# Nodo_univ.net
KiCad netlist of a schematic drawn in EAGLE
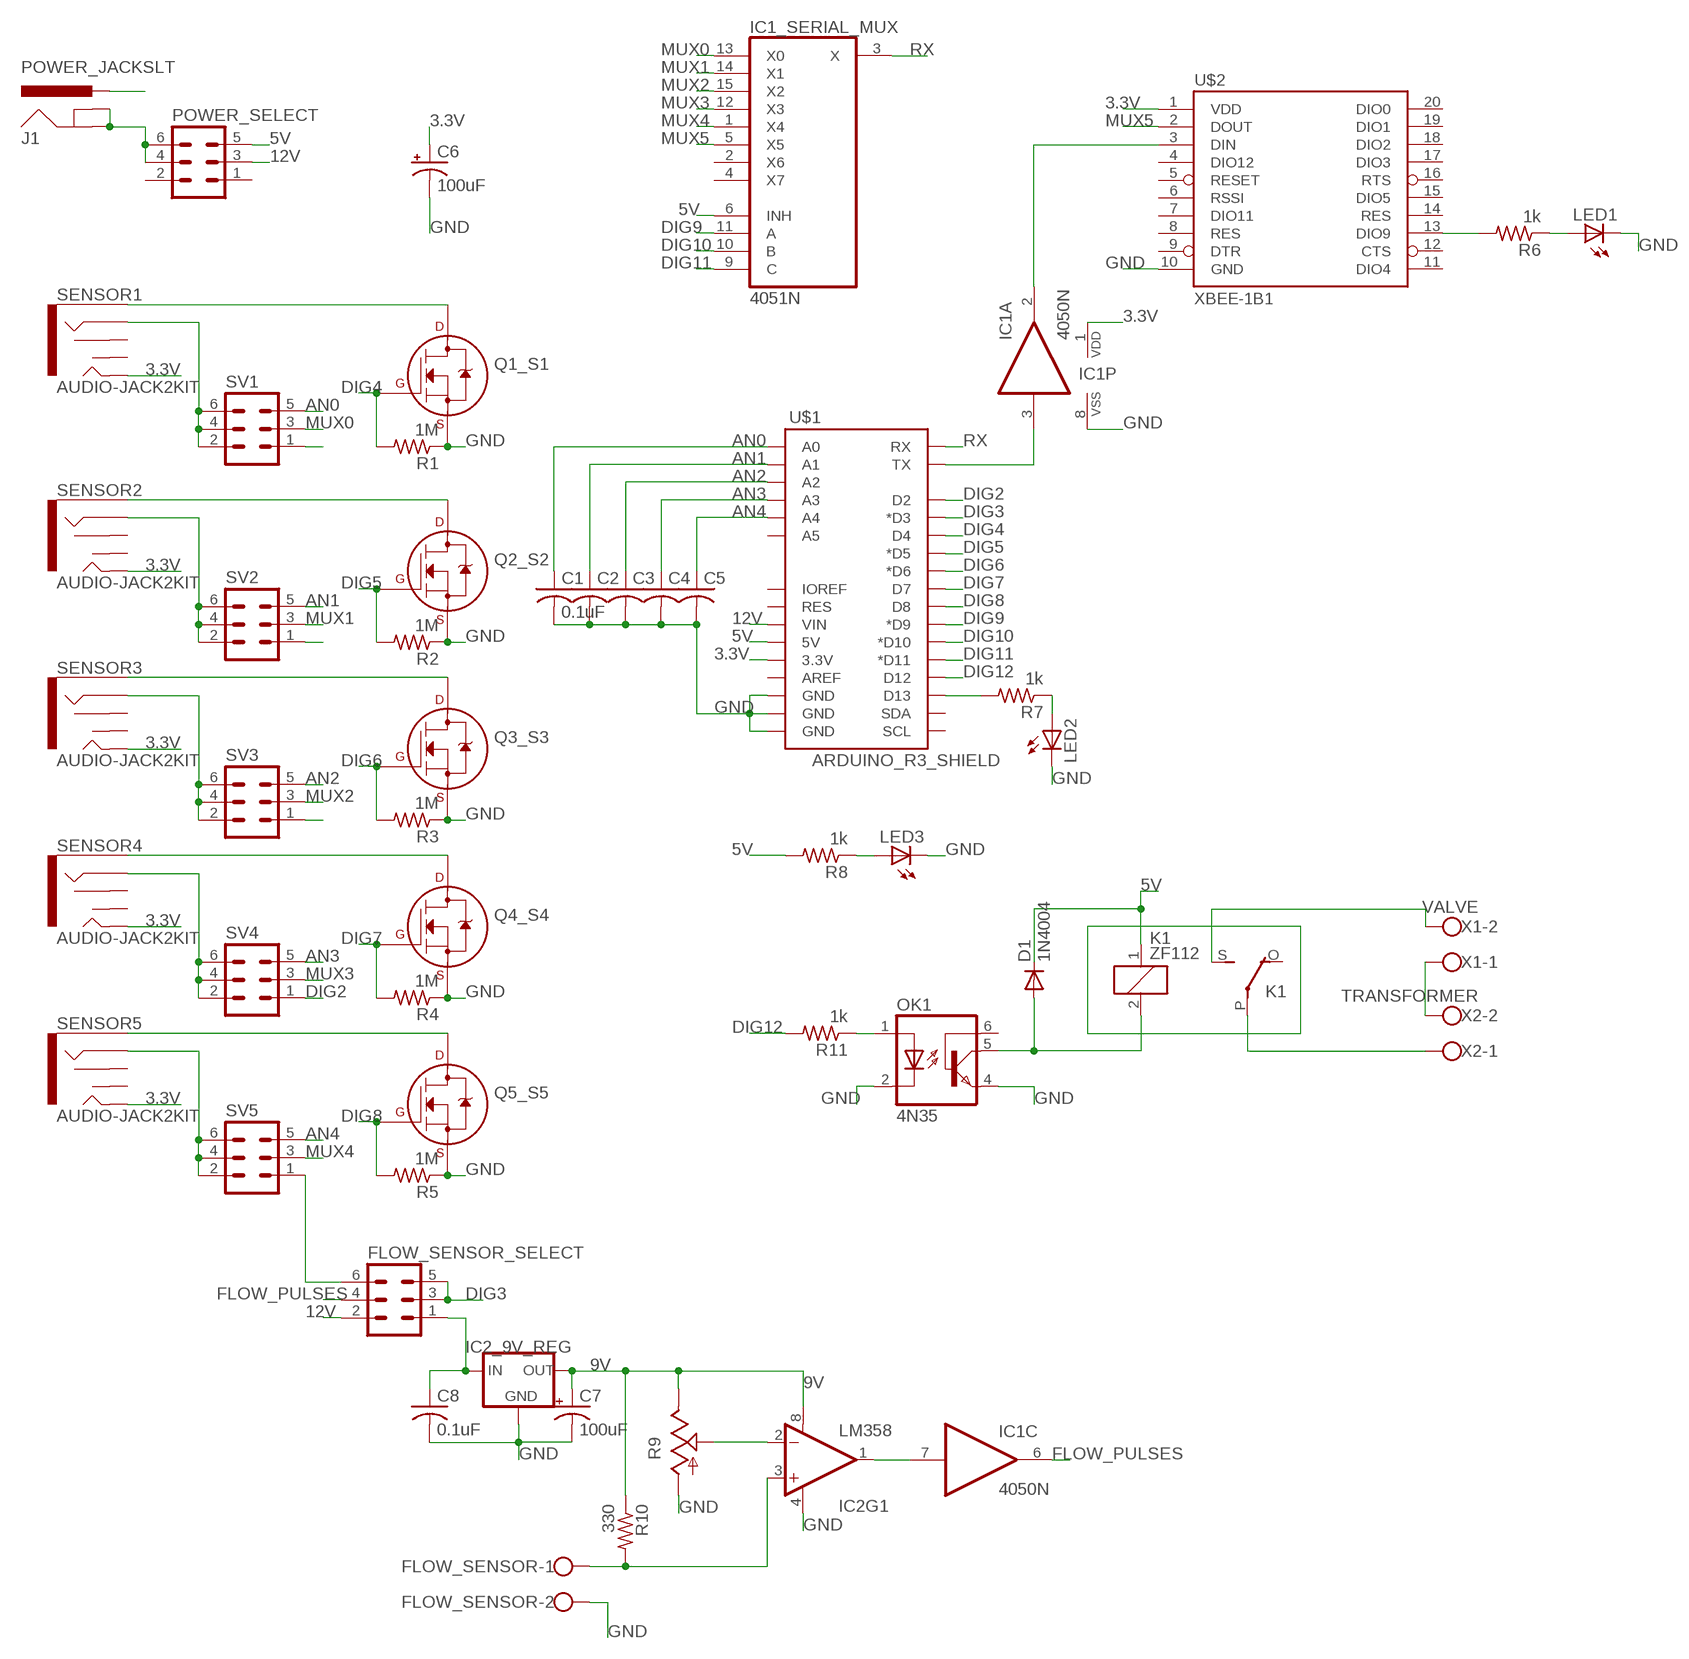
[diagram p0: schematic, sheet 1]

(export (version "E")
  (design (tool "Eeschema 10.0.6"))
  (components
    (comp (ref "C1")
      (value "0.1uF")
      (footprint "eagle-import:C025-025X050")
      (libsource (lib "eagle-import") (part "C-US025-025X050"))
    )
    (comp (ref "C2")
      (value "C-US025-025X050")
      (footprint "eagle-import:C025-025X050")
      (libsource (lib "eagle-import") (part "C-US025-025X050"))
    )
    (comp (ref "C3")
      (value "C-US025-025X050")
      (footprint "eagle-import:C025-025X050")
      (libsource (lib "eagle-import") (part "C-US025-025X050"))
    )
    (comp (ref "C4")
      (value "C-US025-025X050")
      (footprint "eagle-import:C025-025X050")
      (libsource (lib "eagle-import") (part "C-US025-025X050"))
    )
    (comp (ref "C5")
      (value "C-US025-025X050")
      (footprint "eagle-import:C025-025X050")
      (libsource (lib "eagle-import") (part "C-US025-025X050"))
    )
    (comp (ref "C6")
      (value "100uF")
      (footprint "eagle-import:CPOL-RADIAL-100UF-25V")
      (libsource (lib "eagle-import") (part "CAP_POLPTH1"))
    )
    (comp (ref "C7")
      (value "100uF")
      (footprint "eagle-import:CPOL-RADIAL-100UF-25V")
      (libsource (lib "eagle-import") (part "CAP_POLPTH1"))
    )
    (comp (ref "C8")
      (value "0.1uF")
      (footprint "eagle-import:C025-025X050")
      (libsource (lib "eagle-import") (part "C-US025-025X050"))
    )
    (comp (ref "D1")
      (value "1N4004")
      (footprint "eagle-import:DO41-10")
      (libsource (lib "eagle-import") (part "1N4004"))
    )
    (comp (ref "FLOW_SENSOR")
      (value "W237-102")
      (footprint "eagle-import:W237-102")
      (fields (field (name "MPN") "237-102"))
      (libsource (lib "eagle-import") (part "W237-102"))
    )
    (comp (ref "FLOW_SENSOR_SELECT")
      (value "MA03-2")
      (footprint "eagle-import:MA03-2")
      (libsource (lib "eagle-import") (part "MA03-2"))
    )
    (comp (ref "IC1")
      (value "4050N")
      (footprint "eagle-import:DIL16")
      (libsource (lib "eagle-import") (part "4050N"))
    )
    (comp (ref "IC1_SERIAL_MUX")
      (value "4051N")
      (footprint "eagle-import:DIL16")
      (libsource (lib "eagle-import") (part "4051N"))
    )
    (comp (ref "IC2")
      (value "LM358")
      (footprint "eagle-import:DIP08")
      (libsource (lib "eagle-import") (part "LM358"))
    )
    (comp (ref "IC2_9V_REG")
      (value "78XXL")
      (footprint "eagle-import:78XXL")
      (libsource (lib "eagle-import") (part "78XXL"))
    )
    (comp (ref "J1")
      (value "POWER_JACKSLT")
      (footprint "eagle-import:POWER_JACK_SLOT")
      (libsource (lib "eagle-import") (part "POWER_JACKSLT"))
    )
    (comp (ref "K1")
      (value "ZF112")
      (footprint "eagle-import:ZF112")
      (libsource (lib "eagle-import") (part "ZF112"))
    )
    (comp (ref "LED1")
      (value "LED3MM")
      (footprint "eagle-import:LED3MM")
      (libsource (lib "eagle-import") (part "LED3MM"))
    )
    (comp (ref "LED2")
      (value "LED3MM")
      (footprint "eagle-import:LED3MM")
      (libsource (lib "eagle-import") (part "LED3MM"))
    )
    (comp (ref "LED3")
      (value "LED3MM")
      (footprint "eagle-import:LED3MM")
      (libsource (lib "eagle-import") (part "LED3MM"))
    )
    (comp (ref "OK1")
      (value "4N35")
      (footprint "eagle-import:DIL06")
      (fields (field (name "MF") "FAIRCHILD SEMICONDUCTOR"))
      (libsource (lib "eagle-import") (part "4N35"))
    )
    (comp (ref "POWER_SELECT")
      (value "MA03-2")
      (footprint "eagle-import:MA03-2")
      (libsource (lib "eagle-import") (part "MA03-2"))
    )
    (comp (ref "Q1_S1")
      (value "2N7000_TO92")
      (footprint "eagle-import:TO-92")
      (libsource (lib "eagle-import") (part "2N700_TO920"))
    )
    (comp (ref "Q2_S2")
      (value "2N7000_TO92")
      (footprint "eagle-import:TO-92")
      (libsource (lib "eagle-import") (part "2N700_TO920"))
    )
    (comp (ref "Q3_S3")
      (value "2N7000_TO92")
      (footprint "eagle-import:TO-92")
      (libsource (lib "eagle-import") (part "2N700_TO920"))
    )
    (comp (ref "Q4_S4")
      (value "2N7000_TO92")
      (footprint "eagle-import:TO-92")
      (libsource (lib "eagle-import") (part "2N700_TO920"))
    )
    (comp (ref "Q5_S5")
      (value "2N7000_TO92")
      (footprint "eagle-import:TO-92")
      (libsource (lib "eagle-import") (part "2N700_TO920"))
    )
    (comp (ref "R1")
      (value "1M")
      (footprint "eagle-import:0207_10")
      (libsource (lib "eagle-import") (part "R-US_0207/10"))
    )
    (comp (ref "R2")
      (value "1M")
      (footprint "eagle-import:0207_10")
      (libsource (lib "eagle-import") (part "R-US_0207/10"))
    )
    (comp (ref "R3")
      (value "1M")
      (footprint "eagle-import:0207_10")
      (libsource (lib "eagle-import") (part "R-US_0207/10"))
    )
    (comp (ref "R4")
      (value "1M")
      (footprint "eagle-import:0207_10")
      (libsource (lib "eagle-import") (part "R-US_0207/10"))
    )
    (comp (ref "R5")
      (value "1M")
      (footprint "eagle-import:0207_10")
      (libsource (lib "eagle-import") (part "R-US_0207/10"))
    )
    (comp (ref "R6")
      (value "1k")
      (footprint "eagle-import:0207_10")
      (libsource (lib "eagle-import") (part "R-US_0207/10"))
    )
    (comp (ref "R7")
      (value "1k")
      (footprint "eagle-import:0207_10")
      (libsource (lib "eagle-import") (part "R-US_0207/10"))
    )
    (comp (ref "R8")
      (value "1k")
      (footprint "eagle-import:0207_10")
      (libsource (lib "eagle-import") (part "R-US_0207/10"))
    )
    (comp (ref "R9")
      (value "TRIM_US-B64Y")
      (footprint "eagle-import:B64Y")
      (libsource (lib "eagle-import") (part "TRIM_US-B64Y"))
    )
    (comp (ref "R10")
      (value "330")
      (footprint "eagle-import:0207_10")
      (libsource (lib "eagle-import") (part "R-US_0207/10"))
    )
    (comp (ref "R11")
      (value "1k")
      (footprint "eagle-import:0207_10")
      (libsource (lib "eagle-import") (part "R-US_0207/10"))
    )
    (comp (ref "SENSOR1")
      (value "AUDIO-JACK2KIT")
      (footprint "eagle-import:AUDIO-JACK-KIT")
      (libsource (lib "eagle-import") (part "AUDIO-JACK2KIT"))
    )
    (comp (ref "SENSOR2")
      (value "AUDIO-JACK2KIT")
      (footprint "eagle-import:AUDIO-JACK-KIT")
      (libsource (lib "eagle-import") (part "AUDIO-JACK2KIT"))
    )
    (comp (ref "SENSOR3")
      (value "AUDIO-JACK2KIT")
      (footprint "eagle-import:AUDIO-JACK-KIT")
      (libsource (lib "eagle-import") (part "AUDIO-JACK2KIT"))
    )
    (comp (ref "SENSOR4")
      (value "AUDIO-JACK2KIT")
      (footprint "eagle-import:AUDIO-JACK-KIT")
      (libsource (lib "eagle-import") (part "AUDIO-JACK2KIT"))
    )
    (comp (ref "SENSOR5")
      (value "AUDIO-JACK2KIT")
      (footprint "eagle-import:AUDIO-JACK-KIT")
      (libsource (lib "eagle-import") (part "AUDIO-JACK2KIT"))
    )
    (comp (ref "SV1")
      (value "MA03-2")
      (footprint "eagle-import:MA03-2")
      (libsource (lib "eagle-import") (part "MA03-2"))
    )
    (comp (ref "SV2")
      (value "MA03-2")
      (footprint "eagle-import:MA03-2")
      (libsource (lib "eagle-import") (part "MA03-2"))
    )
    (comp (ref "SV3")
      (value "MA03-2")
      (footprint "eagle-import:MA03-2")
      (libsource (lib "eagle-import") (part "MA03-2"))
    )
    (comp (ref "SV4")
      (value "MA03-2")
      (footprint "eagle-import:MA03-2")
      (libsource (lib "eagle-import") (part "MA03-2"))
    )
    (comp (ref "SV5")
      (value "MA03-2")
      (footprint "eagle-import:MA03-2")
      (libsource (lib "eagle-import") (part "MA03-2"))
    )
    (comp (ref "U$1")
      (value "ARDUINO_R3_SHIELD")
      (footprint "eagle-import:UNO_R3_SHIELD")
      (libsource (lib "eagle-import") (part "ARDUINO_R3_SHIELD"))
    )
    (comp (ref "U$2")
      (value "XBEE-1B1")
      (footprint "eagle-import:XBEE-1")
      (libsource (lib "eagle-import") (part "XBEE-1B1"))
    )
    (comp (ref "X1")
      (value "VALVE")
      (footprint "eagle-import:W237-102")
      (fields (field (name "MPN") "237-102"))
      (libsource (lib "eagle-import") (part "W237-102"))
    )
    (comp (ref "X2")
      (value "TRANSFORMER")
      (footprint "eagle-import:W237-102")
      (fields (field (name "MPN") "237-102"))
      (libsource (lib "eagle-import") (part "W237-102"))
    )
  )
  (nets
    (net (code "1") (name "/3.3V") (class "Default")
      (node (ref "C6") (pin "1") (pinfunction "+_1") (pintype "passive"))
      (node (ref "IC1") (pin "1") (pinfunction "VDD_1") (pintype "power_in"))
      (node (ref "SENSOR1") (pin "TIP") (pinfunction "TIP_TIP") (pintype "bidirectional"))
      (node (ref "SENSOR2") (pin "TIP") (pinfunction "TIP_TIP") (pintype "bidirectional"))
      (node (ref "SENSOR3") (pin "TIP") (pinfunction "TIP_TIP") (pintype "bidirectional"))
      (node (ref "SENSOR4") (pin "TIP") (pinfunction "TIP_TIP") (pintype "bidirectional"))
      (node (ref "SENSOR5") (pin "TIP") (pinfunction "TIP_TIP") (pintype "bidirectional"))
      (node (ref "U$1") (pin "3.3V") (pinfunction "3.3V_3.3V") (pintype "bidirectional"))
      (node (ref "U$2") (pin "1") (pinfunction "VDD_1") (pintype "power_in"))
    )
    (net (code "2") (name "/5V") (class "Default")
      (node (ref "D1") (pin "C") (pinfunction "C_C") (pintype "passive"))
      (node (ref "IC1_SERIAL_MUX") (pin "6") (pinfunction "INH_6") (pintype "input"))
      (node (ref "K1") (pin "1") (pinfunction "1_1") (pintype "passive"))
      (node (ref "POWER_SELECT") (pin "5") (pinfunction "5_5") (pintype "passive"))
      (node (ref "R8") (pin "2") (pinfunction "2_2") (pintype "passive"))
      (node (ref "U$1") (pin "5V") (pinfunction "5V_5V") (pintype "bidirectional"))
    )
    (net (code "3") (name "/9V") (class "Default")
      (node (ref "C7") (pin "1") (pinfunction "+_1") (pintype "passive"))
      (node (ref "IC2") (pin "8") (pinfunction "V+_8") (pintype "power_in"))
      (node (ref "IC2_9V_REG") (pin "OUT") (pinfunction "OUT_OUT") (pintype "passive"))
      (node (ref "R10") (pin "1") (pinfunction "1_1") (pintype "passive"))
      (node (ref "R9") (pin "E") (pinfunction "E_E") (pintype "passive"))
    )
    (net (code "4") (name "/12V") (class "Default")
      (node (ref "FLOW_SENSOR_SELECT") (pin "2") (pinfunction "2_2") (pintype "passive"))
      (node (ref "POWER_SELECT") (pin "3") (pinfunction "3_3") (pintype "passive"))
      (node (ref "U$1") (pin "VIN") (pinfunction "VIN_VIN") (pintype "bidirectional"))
    )
    (net (code "5") (name "/AN0") (class "Default")
      (node (ref "C1") (pin "1") (pinfunction "1_1") (pintype "passive"))
      (node (ref "SV1") (pin "5") (pinfunction "5_5") (pintype "passive"))
      (node (ref "U$1") (pin "A0") (pinfunction "A0_A0") (pintype "bidirectional"))
    )
    (net (code "6") (name "/AN1") (class "Default")
      (node (ref "C2") (pin "1") (pinfunction "1_1") (pintype "passive"))
      (node (ref "SV2") (pin "5") (pinfunction "5_5") (pintype "passive"))
      (node (ref "U$1") (pin "A1") (pinfunction "A1_A1") (pintype "bidirectional"))
    )
    (net (code "7") (name "/AN2") (class "Default")
      (node (ref "C3") (pin "1") (pinfunction "1_1") (pintype "passive"))
      (node (ref "SV3") (pin "5") (pinfunction "5_5") (pintype "passive"))
      (node (ref "U$1") (pin "A2") (pinfunction "A2_A2") (pintype "bidirectional"))
    )
    (net (code "8") (name "/AN3") (class "Default")
      (node (ref "C4") (pin "1") (pinfunction "1_1") (pintype "passive"))
      (node (ref "SV4") (pin "5") (pinfunction "5_5") (pintype "passive"))
      (node (ref "U$1") (pin "A3") (pinfunction "A3_A3") (pintype "bidirectional"))
    )
    (net (code "9") (name "/AN4") (class "Default")
      (node (ref "C5") (pin "1") (pinfunction "1_1") (pintype "passive"))
      (node (ref "SV5") (pin "5") (pinfunction "5_5") (pintype "passive"))
      (node (ref "U$1") (pin "A4") (pinfunction "A4_A4") (pintype "bidirectional"))
    )
    (net (code "10") (name "/DIG2") (class "Default")
      (node (ref "SV4") (pin "1") (pinfunction "1_1") (pintype "passive"))
      (node (ref "U$1") (pin "D2") (pinfunction "D2_D2") (pintype "bidirectional"))
    )
    (net (code "11") (name "/DIG3") (class "Default")
      (node (ref "FLOW_SENSOR_SELECT") (pin "3") (pinfunction "3_3") (pintype "passive"))
      (node (ref "FLOW_SENSOR_SELECT") (pin "5") (pinfunction "5_5") (pintype "passive"))
      (node (ref "U$1") (pin "D3") (pinfunction "*D3_D3") (pintype "bidirectional"))
    )
    (net (code "12") (name "/DIG4") (class "Default")
      (node (ref "Q1_S1") (pin "2") (pinfunction "G_2") (pintype "tri_state"))
      (node (ref "R1") (pin "2") (pinfunction "2_2") (pintype "passive"))
      (node (ref "U$1") (pin "D4") (pinfunction "D4_D4") (pintype "bidirectional"))
    )
    (net (code "13") (name "/DIG5") (class "Default")
      (node (ref "Q2_S2") (pin "2") (pinfunction "G_2") (pintype "tri_state"))
      (node (ref "R2") (pin "2") (pinfunction "2_2") (pintype "passive"))
      (node (ref "U$1") (pin "D5") (pinfunction "*D5_D5") (pintype "bidirectional"))
    )
    (net (code "14") (name "/DIG6") (class "Default")
      (node (ref "Q3_S3") (pin "2") (pinfunction "G_2") (pintype "tri_state"))
      (node (ref "R3") (pin "2") (pinfunction "2_2") (pintype "passive"))
      (node (ref "U$1") (pin "D6") (pinfunction "*D6_D6") (pintype "bidirectional"))
    )
    (net (code "15") (name "/DIG7") (class "Default")
      (node (ref "Q4_S4") (pin "2") (pinfunction "G_2") (pintype "tri_state"))
      (node (ref "R4") (pin "2") (pinfunction "2_2") (pintype "passive"))
      (node (ref "U$1") (pin "D7") (pinfunction "D7_D7") (pintype "bidirectional"))
    )
    (net (code "16") (name "/DIG8") (class "Default")
      (node (ref "Q5_S5") (pin "2") (pinfunction "G_2") (pintype "tri_state"))
      (node (ref "R5") (pin "2") (pinfunction "2_2") (pintype "passive"))
      (node (ref "U$1") (pin "D8") (pinfunction "D8_D8") (pintype "bidirectional"))
    )
    (net (code "17") (name "/DIG9") (class "Default")
      (node (ref "IC1_SERIAL_MUX") (pin "11") (pinfunction "A_11") (pintype "input"))
      (node (ref "U$1") (pin "D9") (pinfunction "*D9_D9") (pintype "bidirectional"))
    )
    (net (code "18") (name "/DIG10") (class "Default")
      (node (ref "IC1_SERIAL_MUX") (pin "10") (pinfunction "B_10") (pintype "input"))
      (node (ref "U$1") (pin "D10") (pinfunction "*D10_D10") (pintype "bidirectional"))
    )
    (net (code "19") (name "/DIG11") (class "Default")
      (node (ref "IC1_SERIAL_MUX") (pin "9") (pinfunction "C_9") (pintype "input"))
      (node (ref "U$1") (pin "D11") (pinfunction "*D11_D11") (pintype "bidirectional"))
    )
    (net (code "20") (name "/DIG12") (class "Default")
      (node (ref "R11") (pin "2") (pinfunction "2_2") (pintype "passive"))
      (node (ref "U$1") (pin "D12") (pinfunction "D12_D12") (pintype "bidirectional"))
    )
    (net (code "21") (name "/FLOW_PULSES") (class "Default")
      (node (ref "FLOW_SENSOR_SELECT") (pin "4") (pinfunction "4_4") (pintype "passive"))
      (node (ref "IC1") (pin "6") (pinfunction "O_6") (pintype "output"))
    )
    (net (code "22") (name "/GND") (class "Default")
      (node (ref "C1") (pin "2") (pinfunction "2_2") (pintype "passive"))
      (node (ref "C2") (pin "2") (pinfunction "2_2") (pintype "passive"))
      (node (ref "C3") (pin "2") (pinfunction "2_2") (pintype "passive"))
      (node (ref "C4") (pin "2") (pinfunction "2_2") (pintype "passive"))
      (node (ref "C5") (pin "2") (pinfunction "2_2") (pintype "passive"))
      (node (ref "C6") (pin "2") (pinfunction "-_2") (pintype "passive"))
      (node (ref "C7") (pin "2") (pinfunction "-_2") (pintype "passive"))
      (node (ref "C8") (pin "2") (pinfunction "2_2") (pintype "passive"))
      (node (ref "FLOW_SENSOR") (pin "2") (pinfunction "KL_2") (pintype "passive"))
      (node (ref "IC1") (pin "8") (pinfunction "VSS_8") (pintype "power_in"))
      (node (ref "IC2") (pin "4") (pinfunction "V-_4") (pintype "power_in"))
      (node (ref "IC2_9V_REG") (pin "GND") (pinfunction "GND_GND") (pintype "input"))
      (node (ref "J1") (pin "PWR") (pinfunction "PWR_PWR") (pintype "bidirectional"))
      (node (ref "LED1") (pin "K") (pinfunction "C_K") (pintype "passive"))
      (node (ref "LED2") (pin "K") (pinfunction "C_K") (pintype "passive"))
      (node (ref "LED3") (pin "K") (pinfunction "C_K") (pintype "passive"))
      (node (ref "OK1") (pin "2") (pinfunction "C_2") (pintype "passive"))
      (node (ref "OK1") (pin "4") (pinfunction "EMI_4") (pintype "passive"))
      (node (ref "Q1_S1") (pin "1") (pinfunction "S_1") (pintype "bidirectional"))
      (node (ref "Q2_S2") (pin "1") (pinfunction "S_1") (pintype "bidirectional"))
      (node (ref "Q3_S3") (pin "1") (pinfunction "S_1") (pintype "bidirectional"))
      (node (ref "Q4_S4") (pin "1") (pinfunction "S_1") (pintype "bidirectional"))
      (node (ref "Q5_S5") (pin "1") (pinfunction "S_1") (pintype "bidirectional"))
      (node (ref "R1") (pin "1") (pinfunction "1_1") (pintype "passive"))
      (node (ref "R2") (pin "1") (pinfunction "1_1") (pintype "passive"))
      (node (ref "R3") (pin "1") (pinfunction "1_1") (pintype "passive"))
      (node (ref "R4") (pin "1") (pinfunction "1_1") (pintype "passive"))
      (node (ref "R5") (pin "1") (pinfunction "1_1") (pintype "passive"))
      (node (ref "R9") (pin "A") (pinfunction "A_A") (pintype "passive"))
      (node (ref "U$1") (pin "GND@0") (pinfunction "GND_GND@0") (pintype "bidirectional"))
      (node (ref "U$1") (pin "GND@1") (pinfunction "GND_GND@1") (pintype "bidirectional"))
      (node (ref "U$1") (pin "GND@2") (pinfunction "GND_GND@2") (pintype "bidirectional"))
      (node (ref "U$2") (pin "10") (pinfunction "GND_10") (pintype "power_in"))
    )
    (net (code "23") (name "/MUX0") (class "Default")
      (node (ref "IC1_SERIAL_MUX") (pin "13") (pinfunction "X0_13") (pintype "bidirectional"))
      (node (ref "SV1") (pin "3") (pinfunction "3_3") (pintype "passive"))
    )
    (net (code "24") (name "/MUX1") (class "Default")
      (node (ref "IC1_SERIAL_MUX") (pin "14") (pinfunction "X1_14") (pintype "bidirectional"))
      (node (ref "SV2") (pin "3") (pinfunction "3_3") (pintype "passive"))
    )
    (net (code "25") (name "/MUX2") (class "Default")
      (node (ref "IC1_SERIAL_MUX") (pin "15") (pinfunction "X2_15") (pintype "bidirectional"))
      (node (ref "SV3") (pin "3") (pinfunction "3_3") (pintype "passive"))
    )
    (net (code "26") (name "/MUX3") (class "Default")
      (node (ref "IC1_SERIAL_MUX") (pin "12") (pinfunction "X3_12") (pintype "bidirectional"))
      (node (ref "SV4") (pin "3") (pinfunction "3_3") (pintype "passive"))
    )
    (net (code "27") (name "/MUX4") (class "Default")
      (node (ref "IC1_SERIAL_MUX") (pin "1") (pinfunction "X4_1") (pintype "bidirectional"))
      (node (ref "SV5") (pin "3") (pinfunction "3_3") (pintype "passive"))
    )
    (net (code "28") (name "/MUX5") (class "Default")
      (node (ref "IC1_SERIAL_MUX") (pin "5") (pinfunction "X5_5") (pintype "bidirectional"))
      (node (ref "U$2") (pin "2") (pinfunction "DOUT_2") (pintype "output"))
    )
    (net (code "29") (name "/RX") (class "Default")
      (node (ref "IC1_SERIAL_MUX") (pin "3") (pinfunction "X_3") (pintype "bidirectional"))
      (node (ref "U$1") (pin "RX") (pinfunction "RX_RX") (pintype "bidirectional"))
    )
    (net (code "30") (name "Net-(C8-Pad1)") (class "Default")
      (node (ref "C8") (pin "1") (pinfunction "1_1") (pintype "passive"))
      (node (ref "FLOW_SENSOR_SELECT") (pin "1") (pinfunction "1_1") (pintype "passive"))
      (node (ref "IC2_9V_REG") (pin "IN") (pinfunction "IN_IN") (pintype "input"))
    )
    (net (code "31") (name "Net-(FLOW_SENSORA-KL)") (class "Default")
      (node (ref "FLOW_SENSOR") (pin "1") (pinfunction "KL_1") (pintype "passive"))
      (node (ref "IC2") (pin "3") (pinfunction "+IN_3") (pintype "input"))
      (node (ref "R10") (pin "2") (pinfunction "2_2") (pintype "passive"))
    )
    (net (code "32") (name "Net-(FLOW_SENSOR_SELECT-Pad6)") (class "Default")
      (node (ref "FLOW_SENSOR_SELECT") (pin "6") (pinfunction "6_6") (pintype "passive"))
      (node (ref "SV5") (pin "1") (pinfunction "1_1") (pintype "passive"))
    )
    (net (code "33") (name "Net-(IC1A-I)") (class "Default")
      (node (ref "IC1") (pin "3") (pinfunction "I_3") (pintype "input"))
      (node (ref "U$1") (pin "TX") (pinfunction "TX_TX") (pintype "bidirectional"))
    )
    (net (code "34") (name "Net-(IC1A-O)") (class "Default")
      (node (ref "IC1") (pin "2") (pinfunction "O_2") (pintype "output"))
      (node (ref "U$2") (pin "3") (pinfunction "DIN_3") (pintype "input"))
    )
    (net (code "35") (name "Net-(IC1C-I)") (class "Default")
      (node (ref "IC1") (pin "7") (pinfunction "I_7") (pintype "input"))
      (node (ref "IC2") (pin "1") (pinfunction "OUT_1") (pintype "output"))
    )
    (net (code "36") (name "Net-(IC2A--IN)") (class "Default")
      (node (ref "IC2") (pin "2") (pinfunction "-IN_2") (pintype "input"))
      (node (ref "R9") (pin "S") (pinfunction "S_S") (pintype "passive"))
    )
    (net (code "37") (name "Net-(J1-GND)") (class "Default")
      (node (ref "J1") (pin "GND@1") (pinfunction "GNDBREAK_GND@1") (pintype "bidirectional"))
      (node (ref "J1") (pin "GND@2") (pinfunction "GND_GND@2") (pintype "bidirectional"))
      (node (ref "POWER_SELECT") (pin "4") (pinfunction "4_4") (pintype "passive"))
      (node (ref "POWER_SELECT") (pin "6") (pinfunction "6_6") (pintype "passive"))
    )
    (net (code "38") (name "Net-(LED1-PadA)") (class "Default")
      (node (ref "LED1") (pin "A") (pinfunction "A_A") (pintype "passive"))
      (node (ref "R6") (pin "1") (pinfunction "1_1") (pintype "passive"))
    )
    (net (code "39") (name "Net-(LED2-PadA)") (class "Default")
      (node (ref "LED2") (pin "A") (pinfunction "A_A") (pintype "passive"))
      (node (ref "R7") (pin "1") (pinfunction "1_1") (pintype "passive"))
    )
    (net (code "40") (name "Net-(LED3-PadA)") (class "Default")
      (node (ref "LED3") (pin "A") (pinfunction "A_A") (pintype "passive"))
      (node (ref "R8") (pin "1") (pinfunction "1_1") (pintype "passive"))
    )
    (net (code "41") (name "Net-(OK1-A)") (class "Default")
      (node (ref "OK1") (pin "1") (pinfunction "A_1") (pintype "passive"))
      (node (ref "R11") (pin "1") (pinfunction "1_1") (pintype "passive"))
    )
    (net (code "42") (name "Net-(OK1-COL)") (class "Default")
      (node (ref "D1") (pin "A") (pinfunction "A_A") (pintype "passive"))
      (node (ref "K1") (pin "2") (pinfunction "2_2") (pintype "passive"))
      (node (ref "OK1") (pin "5") (pinfunction "COL_5") (pintype "passive"))
    )
    (net (code "43") (name "Net-(Q1_S1-D)") (class "Default")
      (node (ref "Q1_S1") (pin "3") (pinfunction "D_3") (pintype "bidirectional"))
      (node (ref "SENSOR1") (pin "SLEEVE") (pinfunction "SLEEVE_SLEEVE") (pintype "bidirectional"))
    )
    (net (code "44") (name "Net-(Q2_S2-D)") (class "Default")
      (node (ref "Q2_S2") (pin "3") (pinfunction "D_3") (pintype "bidirectional"))
      (node (ref "SENSOR2") (pin "SLEEVE") (pinfunction "SLEEVE_SLEEVE") (pintype "bidirectional"))
    )
    (net (code "45") (name "Net-(Q3_S3-D)") (class "Default")
      (node (ref "Q3_S3") (pin "3") (pinfunction "D_3") (pintype "bidirectional"))
      (node (ref "SENSOR3") (pin "SLEEVE") (pinfunction "SLEEVE_SLEEVE") (pintype "bidirectional"))
    )
    (net (code "46") (name "Net-(Q4_S4-D)") (class "Default")
      (node (ref "Q4_S4") (pin "3") (pinfunction "D_3") (pintype "bidirectional"))
      (node (ref "SENSOR4") (pin "SLEEVE") (pinfunction "SLEEVE_SLEEVE") (pintype "bidirectional"))
    )
    (net (code "47") (name "Net-(Q5_S5-D)") (class "Default")
      (node (ref "Q5_S5") (pin "3") (pinfunction "D_3") (pintype "bidirectional"))
      (node (ref "SENSOR5") (pin "SLEEVE") (pinfunction "SLEEVE_SLEEVE") (pintype "bidirectional"))
    )
    (net (code "48") (name "Net-(R7-Pad2)") (class "Default")
      (node (ref "R7") (pin "2") (pinfunction "2_2") (pintype "passive"))
      (node (ref "U$1") (pin "D13") (pinfunction "D13_D13") (pintype "bidirectional"))
    )
    (net (code "49") (name "Net-(SENSOR1-PadRING)") (class "Default")
      (node (ref "SENSOR1") (pin "RING") (pinfunction "RING_RING") (pintype "bidirectional"))
      (node (ref "SV1") (pin "2") (pinfunction "2_2") (pintype "passive"))
      (node (ref "SV1") (pin "4") (pinfunction "4_4") (pintype "passive"))
      (node (ref "SV1") (pin "6") (pinfunction "6_6") (pintype "passive"))
    )
    (net (code "50") (name "Net-(SENSOR2-PadRING)") (class "Default")
      (node (ref "SENSOR2") (pin "RING") (pinfunction "RING_RING") (pintype "bidirectional"))
      (node (ref "SV2") (pin "2") (pinfunction "2_2") (pintype "passive"))
      (node (ref "SV2") (pin "4") (pinfunction "4_4") (pintype "passive"))
      (node (ref "SV2") (pin "6") (pinfunction "6_6") (pintype "passive"))
    )
    (net (code "51") (name "Net-(SENSOR3-PadRING)") (class "Default")
      (node (ref "SENSOR3") (pin "RING") (pinfunction "RING_RING") (pintype "bidirectional"))
      (node (ref "SV3") (pin "2") (pinfunction "2_2") (pintype "passive"))
      (node (ref "SV3") (pin "4") (pinfunction "4_4") (pintype "passive"))
      (node (ref "SV3") (pin "6") (pinfunction "6_6") (pintype "passive"))
    )
    (net (code "52") (name "Net-(SENSOR4-PadRING)") (class "Default")
      (node (ref "SENSOR4") (pin "RING") (pinfunction "RING_RING") (pintype "bidirectional"))
      (node (ref "SV4") (pin "2") (pinfunction "2_2") (pintype "passive"))
      (node (ref "SV4") (pin "4") (pinfunction "4_4") (pintype "passive"))
      (node (ref "SV4") (pin "6") (pinfunction "6_6") (pintype "passive"))
    )
    (net (code "53") (name "Net-(SENSOR5-PadRING)") (class "Default")
      (node (ref "SENSOR5") (pin "RING") (pinfunction "RING_RING") (pintype "bidirectional"))
      (node (ref "SV5") (pin "2") (pinfunction "2_2") (pintype "passive"))
      (node (ref "SV5") (pin "4") (pinfunction "4_4") (pintype "passive"))
      (node (ref "SV5") (pin "6") (pinfunction "6_6") (pintype "passive"))
    )
    (net (code "54") (name "Net-(U$2-DIO9)") (class "Default")
      (node (ref "R6") (pin "2") (pinfunction "2_2") (pintype "passive"))
      (node (ref "U$2") (pin "13") (pinfunction "DIO9_13") (pintype "bidirectional"))
    )
    (net (code "55") (name "Net-(X1A-KL)") (class "Default")
      (node (ref "X1") (pin "1") (pinfunction "KL_1") (pintype "passive"))
      (node (ref "X2") (pin "2") (pinfunction "KL_2") (pintype "passive"))
    )
    (net (code "56") (name "Net-(X1B-KL)") (class "Default")
      (node (ref "K1") (pin "S") (pinfunction "S_S") (pintype "passive"))
      (node (ref "X1") (pin "2") (pinfunction "KL_2") (pintype "passive"))
    )
    (net (code "57") (name "Net-(X2A-KL)") (class "Default")
      (node (ref "K1") (pin "P") (pinfunction "P_P") (pintype "passive"))
      (node (ref "X2") (pin "1") (pinfunction "KL_1") (pintype "passive"))
    )
    (net (code "58") (name "unconnected-(IC1_SERIAL_MUXA-X6-Pad2)") (class "Default")
      (node (ref "IC1_SERIAL_MUX") (pin "2") (pinfunction "X6_2") (pintype "bidirectional"))
    )
    (net (code "59") (name "unconnected-(IC1_SERIAL_MUXA-X7-Pad4)") (class "Default")
      (node (ref "IC1_SERIAL_MUX") (pin "4") (pinfunction "X7_4") (pintype "bidirectional"))
    )
    (net (code "60") (name "unconnected-(K1-PadO)") (class "Default")
      (node (ref "K1") (pin "O") (pinfunction "O_O") (pintype "passive"))
    )
    (net (code "61") (name "unconnected-(OK1-BAS-Pad6)") (class "Default")
      (node (ref "OK1") (pin "6") (pinfunction "BAS_6") (pintype "passive"))
    )
    (net (code "62") (name "unconnected-(POWER_SELECT-Pad1)") (class "Default")
      (node (ref "POWER_SELECT") (pin "1") (pinfunction "1_1") (pintype "passive"))
    )
    (net (code "63") (name "unconnected-(POWER_SELECT-Pad2)") (class "Default")
      (node (ref "POWER_SELECT") (pin "2") (pinfunction "2_2") (pintype "passive"))
    )
    (net (code "64") (name "unconnected-(SENSOR1-PadRSH)") (class "Default")
      (node (ref "SENSOR1") (pin "RSH") (pinfunction "RSH_RSH") (pintype "bidirectional"))
    )
    (net (code "65") (name "unconnected-(SENSOR1-PadTSH)") (class "Default")
      (node (ref "SENSOR1") (pin "TSH") (pinfunction "TSH_TSH") (pintype "bidirectional"))
    )
    (net (code "66") (name "unconnected-(SENSOR2-PadRSH)") (class "Default")
      (node (ref "SENSOR2") (pin "RSH") (pinfunction "RSH_RSH") (pintype "bidirectional"))
    )
    (net (code "67") (name "unconnected-(SENSOR2-PadTSH)") (class "Default")
      (node (ref "SENSOR2") (pin "TSH") (pinfunction "TSH_TSH") (pintype "bidirectional"))
    )
    (net (code "68") (name "unconnected-(SENSOR3-PadRSH)") (class "Default")
      (node (ref "SENSOR3") (pin "RSH") (pinfunction "RSH_RSH") (pintype "bidirectional"))
    )
    (net (code "69") (name "unconnected-(SENSOR3-PadTSH)") (class "Default")
      (node (ref "SENSOR3") (pin "TSH") (pinfunction "TSH_TSH") (pintype "bidirectional"))
    )
    (net (code "70") (name "unconnected-(SENSOR4-PadRSH)") (class "Default")
      (node (ref "SENSOR4") (pin "RSH") (pinfunction "RSH_RSH") (pintype "bidirectional"))
    )
    (net (code "71") (name "unconnected-(SENSOR4-PadTSH)") (class "Default")
      (node (ref "SENSOR4") (pin "TSH") (pinfunction "TSH_TSH") (pintype "bidirectional"))
    )
    (net (code "72") (name "unconnected-(SENSOR5-PadRSH)") (class "Default")
      (node (ref "SENSOR5") (pin "RSH") (pinfunction "RSH_RSH") (pintype "bidirectional"))
    )
    (net (code "73") (name "unconnected-(SENSOR5-PadTSH)") (class "Default")
      (node (ref "SENSOR5") (pin "TSH") (pinfunction "TSH_TSH") (pintype "bidirectional"))
    )
    (net (code "74") (name "unconnected-(SV1-Pad1)") (class "Default")
      (node (ref "SV1") (pin "1") (pinfunction "1_1") (pintype "passive"))
    )
    (net (code "75") (name "unconnected-(SV2-Pad1)") (class "Default")
      (node (ref "SV2") (pin "1") (pinfunction "1_1") (pintype "passive"))
    )
    (net (code "76") (name "unconnected-(SV3-Pad1)") (class "Default")
      (node (ref "SV3") (pin "1") (pinfunction "1_1") (pintype "passive"))
    )
    (net (code "77") (name "unconnected-(U$1-PadA5)") (class "Default")
      (node (ref "U$1") (pin "A5") (pinfunction "A5_A5") (pintype "bidirectional"))
    )
    (net (code "78") (name "unconnected-(U$1-PadAREF)") (class "Default")
      (node (ref "U$1") (pin "AREF") (pinfunction "AREF_AREF") (pintype "bidirectional"))
    )
    (net (code "79") (name "unconnected-(U$1-PadIOREF)") (class "Default")
      (node (ref "U$1") (pin "IOREF") (pinfunction "IOREF_IOREF") (pintype "bidirectional"))
    )
    (net (code "80") (name "unconnected-(U$1-PadRES)") (class "Default")
      (node (ref "U$1") (pin "RES") (pinfunction "RES_RES") (pintype "bidirectional"))
    )
    (net (code "81") (name "unconnected-(U$1-PadSCL)") (class "Default")
      (node (ref "U$1") (pin "SCL") (pinfunction "SCL_SCL") (pintype "bidirectional"))
    )
    (net (code "82") (name "unconnected-(U$1-PadSDA)") (class "Default")
      (node (ref "U$1") (pin "SDA") (pinfunction "SDA_SDA") (pintype "bidirectional"))
    )
    (net (code "83") (name "unconnected-(U$2-CTS-Pad12)") (class "Default")
      (node (ref "U$2") (pin "12") (pinfunction "CTS_12") (pintype "output"))
    )
    (net (code "84") (name "unconnected-(U$2-DIO0-Pad20)") (class "Default")
      (node (ref "U$2") (pin "20") (pinfunction "DIO0_20") (pintype "bidirectional"))
    )
    (net (code "85") (name "unconnected-(U$2-DIO1-Pad19)") (class "Default")
      (node (ref "U$2") (pin "19") (pinfunction "DIO1_19") (pintype "bidirectional"))
    )
    (net (code "86") (name "unconnected-(U$2-DIO2-Pad18)") (class "Default")
      (node (ref "U$2") (pin "18") (pinfunction "DIO2_18") (pintype "bidirectional"))
    )
    (net (code "87") (name "unconnected-(U$2-DIO3-Pad17)") (class "Default")
      (node (ref "U$2") (pin "17") (pinfunction "DIO3_17") (pintype "bidirectional"))
    )
    (net (code "88") (name "unconnected-(U$2-DIO4-Pad11)") (class "Default")
      (node (ref "U$2") (pin "11") (pinfunction "DIO4_11") (pintype "bidirectional"))
    )
    (net (code "89") (name "unconnected-(U$2-DIO5-Pad15)") (class "Default")
      (node (ref "U$2") (pin "15") (pinfunction "DIO5_15") (pintype "bidirectional"))
    )
    (net (code "90") (name "unconnected-(U$2-DIO11-Pad7)") (class "Default")
      (node (ref "U$2") (pin "7") (pinfunction "DIO11_7") (pintype "bidirectional"))
    )
    (net (code "91") (name "unconnected-(U$2-DIO12-Pad4)") (class "Default")
      (node (ref "U$2") (pin "4") (pinfunction "DIO12_4") (pintype "bidirectional"))
    )
    (net (code "92") (name "unconnected-(U$2-DTR-Pad9)") (class "Default")
      (node (ref "U$2") (pin "9") (pinfunction "DTR_9") (pintype "bidirectional"))
    )
    (net (code "93") (name "unconnected-(U$2-RES-Pad8)") (class "Default")
      (node (ref "U$2") (pin "8") (pinfunction "RES_8") (pintype "bidirectional"))
    )
    (net (code "94") (name "unconnected-(U$2-RES-Pad14)") (class "Default")
      (node (ref "U$2") (pin "14") (pinfunction "RES_14") (pintype "bidirectional"))
    )
    (net (code "95") (name "unconnected-(U$2-RESET-Pad5)") (class "Default")
      (node (ref "U$2") (pin "5") (pinfunction "RESET_5") (pintype "input"))
    )
    (net (code "96") (name "unconnected-(U$2-RSSI-Pad6)") (class "Default")
      (node (ref "U$2") (pin "6") (pinfunction "RSSI_6") (pintype "bidirectional"))
    )
    (net (code "97") (name "unconnected-(U$2-RTS-Pad16)") (class "Default")
      (node (ref "U$2") (pin "16") (pinfunction "RTS_16") (pintype "input"))
    )
  )
)
